# hivepod_interface_board_v1_1.net
KiCad netlist of a schematic drawn in EAGLE
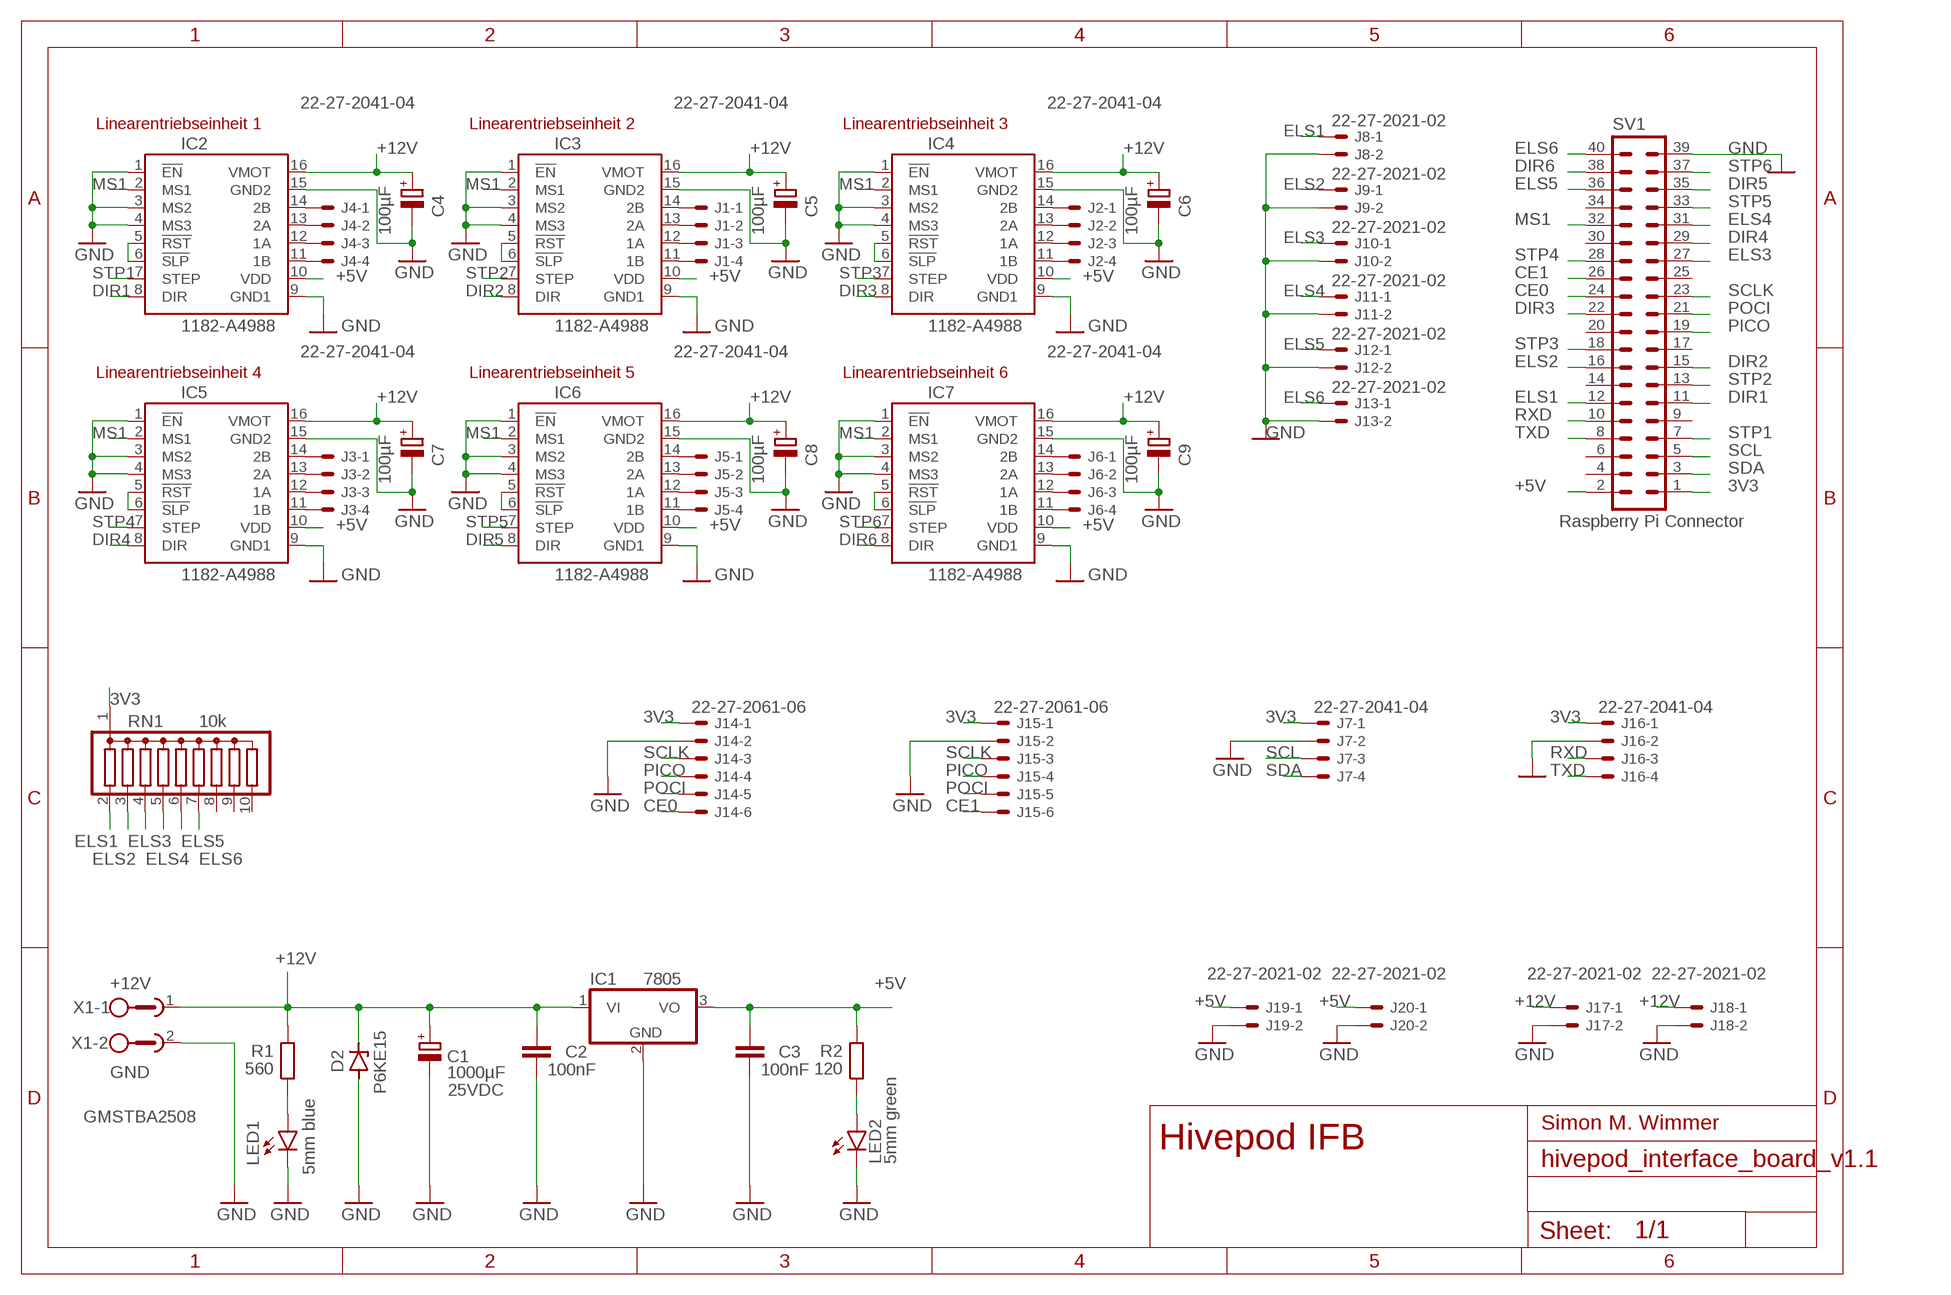
[diagram p0: schematic, sheet 1]

(export (version "E")
  (design (tool "Eeschema 10.0.6"))
  (components
    (comp (ref "C1")
      (value "1000µF")
      (footprint "eagle-import:E5-10,5")
      (libsource (lib "eagle-import") (part "rcl_334_CPOL-EUE5-10.5"))
    )
    (comp (ref "C2")
      (value "100nF")
      (footprint "eagle-import:C1206")
      (libsource (lib "eagle-import") (part "C-EUC1206"))
    )
    (comp (ref "C3")
      (value "100nF")
      (footprint "eagle-import:C1206")
      (libsource (lib "eagle-import") (part "C-EUC1206"))
    )
    (comp (ref "C4")
      (value "100µF")
      (footprint "eagle-import:E5-6")
      (libsource (lib "eagle-import") (part "CPOL-EUE5-6"))
    )
    (comp (ref "C5")
      (value "100µF")
      (footprint "eagle-import:E5-6")
      (libsource (lib "eagle-import") (part "CPOL-EUE5-6"))
    )
    (comp (ref "C6")
      (value "100µF")
      (footprint "eagle-import:E5-6")
      (libsource (lib "eagle-import") (part "CPOL-EUE5-6"))
    )
    (comp (ref "C7")
      (value "100µF")
      (footprint "eagle-import:E5-6")
      (libsource (lib "eagle-import") (part "CPOL-EUE5-6"))
    )
    (comp (ref "C8")
      (value "100µF")
      (footprint "eagle-import:E5-6")
      (libsource (lib "eagle-import") (part "CPOL-EUE5-6"))
    )
    (comp (ref "C9")
      (value "100µF")
      (footprint "eagle-import:E5-6")
      (libsource (lib "eagle-import") (part "CPOL-EUE5-6"))
    )
    (comp (ref "D2")
      (value "P6KE15")
      (footprint "eagle-import:F126Z12")
      (libsource (lib "eagle-import") (part "BZY97"))
    )
    (comp (ref "IC1")
      (value "7805")
      (footprint "eagle-import:TO220V")
      (libsource (lib "eagle-import") (part "78V"))
    )
    (comp (ref "IC2")
      (value "1182-A4988")
      (footprint "eagle-import:A4988")
      (libsource (lib "eagle-import") (part "1182-A4988"))
    )
    (comp (ref "IC3")
      (value "1182-A4988")
      (footprint "eagle-import:A4988")
      (libsource (lib "eagle-import") (part "1182-A4988"))
    )
    (comp (ref "IC4")
      (value "1182-A4988")
      (footprint "eagle-import:A4988")
      (libsource (lib "eagle-import") (part "1182-A4988"))
    )
    (comp (ref "IC5")
      (value "1182-A4988")
      (footprint "eagle-import:A4988")
      (libsource (lib "eagle-import") (part "1182-A4988"))
    )
    (comp (ref "IC6")
      (value "1182-A4988")
      (footprint "eagle-import:A4988")
      (libsource (lib "eagle-import") (part "1182-A4988"))
    )
    (comp (ref "IC7")
      (value "1182-A4988")
      (footprint "eagle-import:A4988")
      (libsource (lib "eagle-import") (part "1182-A4988"))
    )
    (comp (ref "J1")
      (value "22-27-2041-04")
      (footprint "eagle-import:6410-04")
      (fields (field (name "MF") "MOLEX"))
      (libsource (lib "eagle-import") (part "22-?-0427-2041"))
    )
    (comp (ref "J2")
      (value "22-27-2041-04")
      (footprint "eagle-import:6410-04")
      (fields (field (name "MF") "MOLEX"))
      (libsource (lib "eagle-import") (part "22-?-0427-2041"))
    )
    (comp (ref "J3")
      (value "22-27-2041-04")
      (footprint "eagle-import:6410-04")
      (fields (field (name "MF") "MOLEX"))
      (libsource (lib "eagle-import") (part "22-?-0427-2041"))
    )
    (comp (ref "J4")
      (value "22-27-2041-04")
      (footprint "eagle-import:6410-04")
      (fields (field (name "MF") "MOLEX"))
      (libsource (lib "eagle-import") (part "22-?-0427-2041"))
    )
    (comp (ref "J5")
      (value "22-27-2041-04")
      (footprint "eagle-import:6410-04")
      (fields (field (name "MF") "MOLEX"))
      (libsource (lib "eagle-import") (part "22-?-0427-2041"))
    )
    (comp (ref "J6")
      (value "22-27-2041-04")
      (footprint "eagle-import:6410-04")
      (fields (field (name "MF") "MOLEX"))
      (libsource (lib "eagle-import") (part "22-?-0427-2041"))
    )
    (comp (ref "J7")
      (value "22-27-2041-04")
      (footprint "eagle-import:6410-04")
      (fields (field (name "MF") "MOLEX"))
      (libsource (lib "eagle-import") (part "22-?-0427-2041"))
    )
    (comp (ref "J8")
      (value "22-27-2021-02")
      (footprint "eagle-import:6410-02")
      (fields (field (name "MF") "MOLEX"))
      (libsource (lib "eagle-import") (part "22-?-0227-2021"))
    )
    (comp (ref "J9")
      (value "22-27-2021-02")
      (footprint "eagle-import:6410-02")
      (fields (field (name "MF") "MOLEX"))
      (libsource (lib "eagle-import") (part "22-?-0227-2021"))
    )
    (comp (ref "J10")
      (value "22-27-2021-02")
      (footprint "eagle-import:6410-02")
      (fields (field (name "MF") "MOLEX"))
      (libsource (lib "eagle-import") (part "22-?-0227-2021"))
    )
    (comp (ref "J11")
      (value "22-27-2021-02")
      (footprint "eagle-import:6410-02")
      (fields (field (name "MF") "MOLEX"))
      (libsource (lib "eagle-import") (part "22-?-0227-2021"))
    )
    (comp (ref "J12")
      (value "22-27-2021-02")
      (footprint "eagle-import:6410-02")
      (fields (field (name "MF") "MOLEX"))
      (libsource (lib "eagle-import") (part "22-?-0227-2021"))
    )
    (comp (ref "J13")
      (value "22-27-2021-02")
      (footprint "eagle-import:6410-02")
      (fields (field (name "MF") "MOLEX"))
      (libsource (lib "eagle-import") (part "22-?-0227-2021"))
    )
    (comp (ref "J14")
      (value "22-27-2061-06")
      (footprint "eagle-import:6410-06")
      (libsource (lib "eagle-import") (part "22-?-0627-2061"))
    )
    (comp (ref "J15")
      (value "22-27-2061-06")
      (footprint "eagle-import:6410-06")
      (libsource (lib "eagle-import") (part "22-?-0627-2061"))
    )
    (comp (ref "J16")
      (value "22-27-2041-04")
      (footprint "eagle-import:6410-04")
      (fields (field (name "MF") "MOLEX"))
      (libsource (lib "eagle-import") (part "22-?-0427-2041"))
    )
    (comp (ref "J17")
      (value "22-27-2021-02")
      (footprint "eagle-import:6410-02")
      (fields (field (name "MF") "MOLEX"))
      (libsource (lib "eagle-import") (part "22-?-0227-2021"))
    )
    (comp (ref "J18")
      (value "22-27-2021-02")
      (footprint "eagle-import:6410-02")
      (fields (field (name "MF") "MOLEX"))
      (libsource (lib "eagle-import") (part "22-?-0227-2021"))
    )
    (comp (ref "J19")
      (value "22-27-2021-02")
      (footprint "eagle-import:6410-02")
      (fields (field (name "MF") "MOLEX"))
      (libsource (lib "eagle-import") (part "22-?-0227-2021"))
    )
    (comp (ref "J20")
      (value "22-27-2021-02")
      (footprint "eagle-import:6410-02")
      (fields (field (name "MF") "MOLEX"))
      (libsource (lib "eagle-import") (part "22-?-0227-2021"))
    )
    (comp (ref "LED1")
      (value "5mm blue")
      (footprint "eagle-import:LED5MM")
      (libsource (lib "eagle-import") (part "LED5MM"))
    )
    (comp (ref "LED2")
      (value "5mm green")
      (footprint "eagle-import:LED5MM")
      (libsource (lib "eagle-import") (part "LED5MM"))
    )
    (comp (ref "R1")
      (value "560")
      (footprint "eagle-import:R1206")
      (libsource (lib "eagle-import") (part "R-EU_R1206"))
    )
    (comp (ref "R2")
      (value "120")
      (footprint "eagle-import:R1206")
      (libsource (lib "eagle-import") (part "R-EU_R1206"))
    )
    (comp (ref "RN1")
      (value "10k")
      (footprint "eagle-import:SIL10")
      (libsource (lib "eagle-import") (part "G09R"))
    )
    (comp (ref "SV1")
      (value "Raspberry Pi Connector")
      (footprint "eagle-import:ML40")
      (libsource (lib "eagle-import") (part "ML40"))
    )
    (comp (ref "X1")
      (value "GMSTBA2508")
      (footprint "eagle-import:HOR-2")
      (libsource (lib "eagle-import") (part "GMSTBA2508"))
    )
  )
  (nets
    (net (code "1") (name "/+5V") (class "Default")
      (node (ref "C3") (pin "1") (pinfunction "1_1") (pintype "passive"))
      (node (ref "IC1") (pin "3") (pinfunction "VO_3") (pintype "passive"))
      (node (ref "IC2") (pin "10") (pinfunction "VDD_10") (pintype "power_in"))
      (node (ref "IC3") (pin "10") (pinfunction "VDD_10") (pintype "power_in"))
      (node (ref "IC4") (pin "10") (pinfunction "VDD_10") (pintype "power_in"))
      (node (ref "IC5") (pin "10") (pinfunction "VDD_10") (pintype "power_in"))
      (node (ref "IC6") (pin "10") (pinfunction "VDD_10") (pintype "power_in"))
      (node (ref "IC7") (pin "10") (pinfunction "VDD_10") (pintype "power_in"))
      (node (ref "J19") (pin "1") (pinfunction "S_1") (pintype "passive"))
      (node (ref "J20") (pin "1") (pinfunction "S_1") (pintype "passive"))
      (node (ref "R2") (pin "2") (pinfunction "2_2") (pintype "passive"))
      (node (ref "SV1") (pin "2") (pinfunction "2_2") (pintype "passive"))
    )
    (net (code "2") (name "/+12V") (class "Default")
      (node (ref "C1") (pin "+") (pinfunction "+_+") (pintype "passive"))
      (node (ref "C2") (pin "1") (pinfunction "1_1") (pintype "passive"))
      (node (ref "C4") (pin "+") (pinfunction "+_+") (pintype "passive"))
      (node (ref "C5") (pin "+") (pinfunction "+_+") (pintype "passive"))
      (node (ref "C6") (pin "+") (pinfunction "+_+") (pintype "passive"))
      (node (ref "C7") (pin "+") (pinfunction "+_+") (pintype "passive"))
      (node (ref "C8") (pin "+") (pinfunction "+_+") (pintype "passive"))
      (node (ref "C9") (pin "+") (pinfunction "+_+") (pintype "passive"))
      (node (ref "D2") (pin "C") (pinfunction "C_C") (pintype "passive"))
      (node (ref "IC1") (pin "1") (pinfunction "VI_1") (pintype "input"))
      (node (ref "IC2") (pin "16") (pinfunction "VMOT_16") (pintype "power_in"))
      (node (ref "IC3") (pin "16") (pinfunction "VMOT_16") (pintype "power_in"))
      (node (ref "IC4") (pin "16") (pinfunction "VMOT_16") (pintype "power_in"))
      (node (ref "IC5") (pin "16") (pinfunction "VMOT_16") (pintype "power_in"))
      (node (ref "IC6") (pin "16") (pinfunction "VMOT_16") (pintype "power_in"))
      (node (ref "IC7") (pin "16") (pinfunction "VMOT_16") (pintype "power_in"))
      (node (ref "J17") (pin "1") (pinfunction "S_1") (pintype "passive"))
      (node (ref "J18") (pin "1") (pinfunction "S_1") (pintype "passive"))
      (node (ref "R1") (pin "2") (pinfunction "2_2") (pintype "passive"))
      (node (ref "X1") (pin "1") (pinfunction "1_1") (pintype "passive"))
    )
    (net (code "3") (name "/3V3") (class "Default")
      (node (ref "J14") (pin "1") (pinfunction "S_1") (pintype "passive"))
      (node (ref "J15") (pin "1") (pinfunction "S_1") (pintype "passive"))
      (node (ref "J16") (pin "1") (pinfunction "S_1") (pintype "passive"))
      (node (ref "J7") (pin "1") (pinfunction "S_1") (pintype "passive"))
      (node (ref "RN1") (pin "1") (pinfunction "1_1") (pintype "passive"))
      (node (ref "SV1") (pin "1") (pinfunction "1_1") (pintype "passive"))
    )
    (net (code "4") (name "/CE0") (class "Default")
      (node (ref "J14") (pin "6") (pinfunction "S_6") (pintype "passive"))
      (node (ref "SV1") (pin "24") (pinfunction "24_24") (pintype "passive"))
    )
    (net (code "5") (name "/CE1") (class "Default")
      (node (ref "J15") (pin "6") (pinfunction "S_6") (pintype "passive"))
      (node (ref "SV1") (pin "26") (pinfunction "26_26") (pintype "passive"))
    )
    (net (code "6") (name "/DIR1") (class "Default")
      (node (ref "IC2") (pin "8") (pinfunction "DIR_8") (pintype "input"))
      (node (ref "SV1") (pin "11") (pinfunction "11_11") (pintype "passive"))
    )
    (net (code "7") (name "/DIR2") (class "Default")
      (node (ref "IC3") (pin "8") (pinfunction "DIR_8") (pintype "input"))
      (node (ref "SV1") (pin "15") (pinfunction "15_15") (pintype "passive"))
    )
    (net (code "8") (name "/DIR3") (class "Default")
      (node (ref "IC4") (pin "8") (pinfunction "DIR_8") (pintype "input"))
      (node (ref "SV1") (pin "22") (pinfunction "22_22") (pintype "passive"))
    )
    (net (code "9") (name "/DIR4") (class "Default")
      (node (ref "IC5") (pin "8") (pinfunction "DIR_8") (pintype "input"))
      (node (ref "SV1") (pin "29") (pinfunction "29_29") (pintype "passive"))
    )
    (net (code "10") (name "/DIR5") (class "Default")
      (node (ref "IC6") (pin "8") (pinfunction "DIR_8") (pintype "input"))
      (node (ref "SV1") (pin "35") (pinfunction "35_35") (pintype "passive"))
    )
    (net (code "11") (name "/DIR6") (class "Default")
      (node (ref "IC7") (pin "8") (pinfunction "DIR_8") (pintype "input"))
      (node (ref "SV1") (pin "38") (pinfunction "38_38") (pintype "passive"))
    )
    (net (code "12") (name "/ELS1") (class "Default")
      (node (ref "J8") (pin "1") (pinfunction "S_1") (pintype "passive"))
      (node (ref "RN1") (pin "2") (pinfunction "2_2") (pintype "passive"))
      (node (ref "SV1") (pin "12") (pinfunction "12_12") (pintype "passive"))
    )
    (net (code "13") (name "/ELS2") (class "Default")
      (node (ref "J9") (pin "1") (pinfunction "S_1") (pintype "passive"))
      (node (ref "RN1") (pin "3") (pinfunction "3_3") (pintype "passive"))
      (node (ref "SV1") (pin "16") (pinfunction "16_16") (pintype "passive"))
    )
    (net (code "14") (name "/ELS3") (class "Default")
      (node (ref "J10") (pin "1") (pinfunction "S_1") (pintype "passive"))
      (node (ref "RN1") (pin "4") (pinfunction "4_4") (pintype "passive"))
      (node (ref "SV1") (pin "27") (pinfunction "27_27") (pintype "passive"))
    )
    (net (code "15") (name "/ELS4") (class "Default")
      (node (ref "J11") (pin "1") (pinfunction "S_1") (pintype "passive"))
      (node (ref "RN1") (pin "5") (pinfunction "5_5") (pintype "passive"))
      (node (ref "SV1") (pin "31") (pinfunction "31_31") (pintype "passive"))
    )
    (net (code "16") (name "/ELS5") (class "Default")
      (node (ref "J12") (pin "1") (pinfunction "S_1") (pintype "passive"))
      (node (ref "RN1") (pin "6") (pinfunction "6_6") (pintype "passive"))
      (node (ref "SV1") (pin "36") (pinfunction "36_36") (pintype "passive"))
    )
    (net (code "17") (name "/ELS6") (class "Default")
      (node (ref "J13") (pin "1") (pinfunction "S_1") (pintype "passive"))
      (node (ref "RN1") (pin "7") (pinfunction "7_7") (pintype "passive"))
      (node (ref "SV1") (pin "40") (pinfunction "40_40") (pintype "passive"))
    )
    (net (code "18") (name "/MS1") (class "Default")
      (node (ref "IC2") (pin "2") (pinfunction "MS1_2") (pintype "passive"))
      (node (ref "IC3") (pin "2") (pinfunction "MS1_2") (pintype "passive"))
      (node (ref "IC4") (pin "2") (pinfunction "MS1_2") (pintype "passive"))
      (node (ref "IC5") (pin "2") (pinfunction "MS1_2") (pintype "passive"))
      (node (ref "IC6") (pin "2") (pinfunction "MS1_2") (pintype "passive"))
      (node (ref "IC7") (pin "2") (pinfunction "MS1_2") (pintype "passive"))
      (node (ref "SV1") (pin "32") (pinfunction "32_32") (pintype "passive"))
    )
    (net (code "19") (name "/PICO") (class "Default")
      (node (ref "J14") (pin "4") (pinfunction "S_4") (pintype "passive"))
      (node (ref "J15") (pin "4") (pinfunction "S_4") (pintype "passive"))
      (node (ref "SV1") (pin "19") (pinfunction "19_19") (pintype "passive"))
    )
    (net (code "20") (name "/POCI") (class "Default")
      (node (ref "J14") (pin "5") (pinfunction "S_5") (pintype "passive"))
      (node (ref "J15") (pin "5") (pinfunction "S_5") (pintype "passive"))
      (node (ref "SV1") (pin "21") (pinfunction "21_21") (pintype "passive"))
    )
    (net (code "21") (name "/RXD") (class "Default")
      (node (ref "J16") (pin "3") (pinfunction "S_3") (pintype "passive"))
      (node (ref "SV1") (pin "10") (pinfunction "10_10") (pintype "passive"))
    )
    (net (code "22") (name "/SCL") (class "Default")
      (node (ref "J7") (pin "3") (pinfunction "S_3") (pintype "passive"))
      (node (ref "SV1") (pin "5") (pinfunction "5_5") (pintype "passive"))
    )
    (net (code "23") (name "/SCLK") (class "Default")
      (node (ref "J14") (pin "3") (pinfunction "S_3") (pintype "passive"))
      (node (ref "J15") (pin "3") (pinfunction "S_3") (pintype "passive"))
      (node (ref "SV1") (pin "23") (pinfunction "23_23") (pintype "passive"))
    )
    (net (code "24") (name "/SDA") (class "Default")
      (node (ref "J7") (pin "4") (pinfunction "S_4") (pintype "passive"))
      (node (ref "SV1") (pin "3") (pinfunction "3_3") (pintype "passive"))
    )
    (net (code "25") (name "/STP1") (class "Default")
      (node (ref "IC2") (pin "7") (pinfunction "STEP_7") (pintype "input"))
      (node (ref "SV1") (pin "7") (pinfunction "7_7") (pintype "passive"))
    )
    (net (code "26") (name "/STP2") (class "Default")
      (node (ref "IC3") (pin "7") (pinfunction "STEP_7") (pintype "input"))
      (node (ref "SV1") (pin "13") (pinfunction "13_13") (pintype "passive"))
    )
    (net (code "27") (name "/STP3") (class "Default")
      (node (ref "IC4") (pin "7") (pinfunction "STEP_7") (pintype "input"))
      (node (ref "SV1") (pin "18") (pinfunction "18_18") (pintype "passive"))
    )
    (net (code "28") (name "/STP4") (class "Default")
      (node (ref "IC5") (pin "7") (pinfunction "STEP_7") (pintype "input"))
      (node (ref "SV1") (pin "28") (pinfunction "28_28") (pintype "passive"))
    )
    (net (code "29") (name "/STP5") (class "Default")
      (node (ref "IC6") (pin "7") (pinfunction "STEP_7") (pintype "input"))
      (node (ref "SV1") (pin "33") (pinfunction "33_33") (pintype "passive"))
    )
    (net (code "30") (name "/STP6") (class "Default")
      (node (ref "IC7") (pin "7") (pinfunction "STEP_7") (pintype "input"))
      (node (ref "SV1") (pin "37") (pinfunction "37_37") (pintype "passive"))
    )
    (net (code "31") (name "/TXD") (class "Default")
      (node (ref "J16") (pin "4") (pinfunction "S_4") (pintype "passive"))
      (node (ref "SV1") (pin "8") (pinfunction "8_8") (pintype "passive"))
    )
    (net (code "32") (name "GND") (class "Default")
      (node (ref "C1") (pin "-") (pinfunction "-_-") (pintype "passive"))
      (node (ref "C2") (pin "2") (pinfunction "2_2") (pintype "passive"))
      (node (ref "C3") (pin "2") (pinfunction "2_2") (pintype "passive"))
      (node (ref "C4") (pin "-") (pinfunction "-_-") (pintype "passive"))
      (node (ref "C5") (pin "-") (pinfunction "-_-") (pintype "passive"))
      (node (ref "C6") (pin "-") (pinfunction "-_-") (pintype "passive"))
      (node (ref "C7") (pin "-") (pinfunction "-_-") (pintype "passive"))
      (node (ref "C8") (pin "-") (pinfunction "-_-") (pintype "passive"))
      (node (ref "C9") (pin "-") (pinfunction "-_-") (pintype "passive"))
      (node (ref "D2") (pin "A") (pinfunction "A_A") (pintype "passive"))
      (node (ref "IC1") (pin "2") (pinfunction "GND_2") (pintype "passive"))
      (node (ref "IC2") (pin "1") (pinfunction "~{EN}_1") (pintype "passive"))
      (node (ref "IC2") (pin "15") (pinfunction "GND2_15") (pintype "power_in"))
      (node (ref "IC2") (pin "3") (pinfunction "MS2_3") (pintype "passive"))
      (node (ref "IC2") (pin "4") (pinfunction "MS3_4") (pintype "passive"))
      (node (ref "IC2") (pin "9") (pinfunction "GND1_9") (pintype "power_in"))
      (node (ref "IC3") (pin "1") (pinfunction "~{EN}_1") (pintype "passive"))
      (node (ref "IC3") (pin "15") (pinfunction "GND2_15") (pintype "power_in"))
      (node (ref "IC3") (pin "3") (pinfunction "MS2_3") (pintype "passive"))
      (node (ref "IC3") (pin "4") (pinfunction "MS3_4") (pintype "passive"))
      (node (ref "IC3") (pin "9") (pinfunction "GND1_9") (pintype "power_in"))
      (node (ref "IC4") (pin "1") (pinfunction "~{EN}_1") (pintype "passive"))
      (node (ref "IC4") (pin "15") (pinfunction "GND2_15") (pintype "power_in"))
      (node (ref "IC4") (pin "3") (pinfunction "MS2_3") (pintype "passive"))
      (node (ref "IC4") (pin "4") (pinfunction "MS3_4") (pintype "passive"))
      (node (ref "IC4") (pin "9") (pinfunction "GND1_9") (pintype "power_in"))
      (node (ref "IC5") (pin "1") (pinfunction "~{EN}_1") (pintype "passive"))
      (node (ref "IC5") (pin "15") (pinfunction "GND2_15") (pintype "power_in"))
      (node (ref "IC5") (pin "3") (pinfunction "MS2_3") (pintype "passive"))
      (node (ref "IC5") (pin "4") (pinfunction "MS3_4") (pintype "passive"))
      (node (ref "IC5") (pin "9") (pinfunction "GND1_9") (pintype "power_in"))
      (node (ref "IC6") (pin "1") (pinfunction "~{EN}_1") (pintype "passive"))
      (node (ref "IC6") (pin "15") (pinfunction "GND2_15") (pintype "power_in"))
      (node (ref "IC6") (pin "3") (pinfunction "MS2_3") (pintype "passive"))
      (node (ref "IC6") (pin "4") (pinfunction "MS3_4") (pintype "passive"))
      (node (ref "IC6") (pin "9") (pinfunction "GND1_9") (pintype "power_in"))
      (node (ref "IC7") (pin "1") (pinfunction "~{EN}_1") (pintype "passive"))
      (node (ref "IC7") (pin "15") (pinfunction "GND2_15") (pintype "power_in"))
      (node (ref "IC7") (pin "3") (pinfunction "MS2_3") (pintype "passive"))
      (node (ref "IC7") (pin "4") (pinfunction "MS3_4") (pintype "passive"))
      (node (ref "IC7") (pin "9") (pinfunction "GND1_9") (pintype "power_in"))
      (node (ref "J10") (pin "2") (pinfunction "S_2") (pintype "passive"))
      (node (ref "J11") (pin "2") (pinfunction "S_2") (pintype "passive"))
      (node (ref "J12") (pin "2") (pinfunction "S_2") (pintype "passive"))
      (node (ref "J13") (pin "2") (pinfunction "S_2") (pintype "passive"))
      (node (ref "J14") (pin "2") (pinfunction "S_2") (pintype "passive"))
      (node (ref "J15") (pin "2") (pinfunction "S_2") (pintype "passive"))
      (node (ref "J16") (pin "2") (pinfunction "S_2") (pintype "passive"))
      (node (ref "J17") (pin "2") (pinfunction "S_2") (pintype "passive"))
      (node (ref "J18") (pin "2") (pinfunction "S_2") (pintype "passive"))
      (node (ref "J19") (pin "2") (pinfunction "S_2") (pintype "passive"))
      (node (ref "J20") (pin "2") (pinfunction "S_2") (pintype "passive"))
      (node (ref "J7") (pin "2") (pinfunction "S_2") (pintype "passive"))
      (node (ref "J8") (pin "2") (pinfunction "S_2") (pintype "passive"))
      (node (ref "J9") (pin "2") (pinfunction "S_2") (pintype "passive"))
      (node (ref "LED1") (pin "K") (pinfunction "C_K") (pintype "passive"))
      (node (ref "LED2") (pin "K") (pinfunction "C_K") (pintype "passive"))
      (node (ref "SV1") (pin "39") (pinfunction "39_39") (pintype "passive"))
      (node (ref "X1") (pin "2") (pinfunction "1_2") (pintype "passive"))
    )
    (net (code "33") (name "Net-(IC2-1A)") (class "Default")
      (node (ref "IC2") (pin "12") (pinfunction "1A_12") (pintype "output"))
      (node (ref "J4") (pin "3") (pinfunction "S_3") (pintype "passive"))
    )
    (net (code "34") (name "Net-(IC2-1B)") (class "Default")
      (node (ref "IC2") (pin "11") (pinfunction "1B_11") (pintype "output"))
      (node (ref "J4") (pin "4") (pinfunction "S_4") (pintype "passive"))
    )
    (net (code "35") (name "Net-(IC2-2A)") (class "Default")
      (node (ref "IC2") (pin "13") (pinfunction "2A_13") (pintype "output"))
      (node (ref "J4") (pin "2") (pinfunction "S_2") (pintype "passive"))
    )
    (net (code "36") (name "Net-(IC2-2B)") (class "Default")
      (node (ref "IC2") (pin "14") (pinfunction "2B_14") (pintype "output"))
      (node (ref "J4") (pin "1") (pinfunction "S_1") (pintype "passive"))
    )
    (net (code "37") (name "Net-(IC2-~{RST})") (class "Default")
      (node (ref "IC2") (pin "5") (pinfunction "~{RST}_5") (pintype "passive"))
      (node (ref "IC2") (pin "6") (pinfunction "~{SLP}_6") (pintype "passive"))
    )
    (net (code "38") (name "Net-(IC3-1A)") (class "Default")
      (node (ref "IC3") (pin "12") (pinfunction "1A_12") (pintype "output"))
      (node (ref "J1") (pin "3") (pinfunction "S_3") (pintype "passive"))
    )
    (net (code "39") (name "Net-(IC3-1B)") (class "Default")
      (node (ref "IC3") (pin "11") (pinfunction "1B_11") (pintype "output"))
      (node (ref "J1") (pin "4") (pinfunction "S_4") (pintype "passive"))
    )
    (net (code "40") (name "Net-(IC3-2A)") (class "Default")
      (node (ref "IC3") (pin "13") (pinfunction "2A_13") (pintype "output"))
      (node (ref "J1") (pin "2") (pinfunction "S_2") (pintype "passive"))
    )
    (net (code "41") (name "Net-(IC3-2B)") (class "Default")
      (node (ref "IC3") (pin "14") (pinfunction "2B_14") (pintype "output"))
      (node (ref "J1") (pin "1") (pinfunction "S_1") (pintype "passive"))
    )
    (net (code "42") (name "Net-(IC3-~{RST})") (class "Default")
      (node (ref "IC3") (pin "5") (pinfunction "~{RST}_5") (pintype "passive"))
      (node (ref "IC3") (pin "6") (pinfunction "~{SLP}_6") (pintype "passive"))
    )
    (net (code "43") (name "Net-(IC4-1A)") (class "Default")
      (node (ref "IC4") (pin "12") (pinfunction "1A_12") (pintype "output"))
      (node (ref "J2") (pin "3") (pinfunction "S_3") (pintype "passive"))
    )
    (net (code "44") (name "Net-(IC4-1B)") (class "Default")
      (node (ref "IC4") (pin "11") (pinfunction "1B_11") (pintype "output"))
      (node (ref "J2") (pin "4") (pinfunction "S_4") (pintype "passive"))
    )
    (net (code "45") (name "Net-(IC4-2A)") (class "Default")
      (node (ref "IC4") (pin "13") (pinfunction "2A_13") (pintype "output"))
      (node (ref "J2") (pin "2") (pinfunction "S_2") (pintype "passive"))
    )
    (net (code "46") (name "Net-(IC4-2B)") (class "Default")
      (node (ref "IC4") (pin "14") (pinfunction "2B_14") (pintype "output"))
      (node (ref "J2") (pin "1") (pinfunction "S_1") (pintype "passive"))
    )
    (net (code "47") (name "Net-(IC4-~{RST})") (class "Default")
      (node (ref "IC4") (pin "5") (pinfunction "~{RST}_5") (pintype "passive"))
      (node (ref "IC4") (pin "6") (pinfunction "~{SLP}_6") (pintype "passive"))
    )
    (net (code "48") (name "Net-(IC5-1A)") (class "Default")
      (node (ref "IC5") (pin "12") (pinfunction "1A_12") (pintype "output"))
      (node (ref "J3") (pin "3") (pinfunction "S_3") (pintype "passive"))
    )
    (net (code "49") (name "Net-(IC5-1B)") (class "Default")
      (node (ref "IC5") (pin "11") (pinfunction "1B_11") (pintype "output"))
      (node (ref "J3") (pin "4") (pinfunction "S_4") (pintype "passive"))
    )
    (net (code "50") (name "Net-(IC5-2A)") (class "Default")
      (node (ref "IC5") (pin "13") (pinfunction "2A_13") (pintype "output"))
      (node (ref "J3") (pin "2") (pinfunction "S_2") (pintype "passive"))
    )
    (net (code "51") (name "Net-(IC5-2B)") (class "Default")
      (node (ref "IC5") (pin "14") (pinfunction "2B_14") (pintype "output"))
      (node (ref "J3") (pin "1") (pinfunction "S_1") (pintype "passive"))
    )
    (net (code "52") (name "Net-(IC5-~{RST})") (class "Default")
      (node (ref "IC5") (pin "5") (pinfunction "~{RST}_5") (pintype "passive"))
      (node (ref "IC5") (pin "6") (pinfunction "~{SLP}_6") (pintype "passive"))
    )
    (net (code "53") (name "Net-(IC6-1A)") (class "Default")
      (node (ref "IC6") (pin "12") (pinfunction "1A_12") (pintype "output"))
      (node (ref "J5") (pin "3") (pinfunction "S_3") (pintype "passive"))
    )
    (net (code "54") (name "Net-(IC6-1B)") (class "Default")
      (node (ref "IC6") (pin "11") (pinfunction "1B_11") (pintype "output"))
      (node (ref "J5") (pin "4") (pinfunction "S_4") (pintype "passive"))
    )
    (net (code "55") (name "Net-(IC6-2A)") (class "Default")
      (node (ref "IC6") (pin "13") (pinfunction "2A_13") (pintype "output"))
      (node (ref "J5") (pin "2") (pinfunction "S_2") (pintype "passive"))
    )
    (net (code "56") (name "Net-(IC6-2B)") (class "Default")
      (node (ref "IC6") (pin "14") (pinfunction "2B_14") (pintype "output"))
      (node (ref "J5") (pin "1") (pinfunction "S_1") (pintype "passive"))
    )
    (net (code "57") (name "Net-(IC6-~{RST})") (class "Default")
      (node (ref "IC6") (pin "5") (pinfunction "~{RST}_5") (pintype "passive"))
      (node (ref "IC6") (pin "6") (pinfunction "~{SLP}_6") (pintype "passive"))
    )
    (net (code "58") (name "Net-(IC7-1A)") (class "Default")
      (node (ref "IC7") (pin "12") (pinfunction "1A_12") (pintype "output"))
      (node (ref "J6") (pin "3") (pinfunction "S_3") (pintype "passive"))
    )
    (net (code "59") (name "Net-(IC7-1B)") (class "Default")
      (node (ref "IC7") (pin "11") (pinfunction "1B_11") (pintype "output"))
      (node (ref "J6") (pin "4") (pinfunction "S_4") (pintype "passive"))
    )
    (net (code "60") (name "Net-(IC7-2A)") (class "Default")
      (node (ref "IC7") (pin "13") (pinfunction "2A_13") (pintype "output"))
      (node (ref "J6") (pin "2") (pinfunction "S_2") (pintype "passive"))
    )
    (net (code "61") (name "Net-(IC7-2B)") (class "Default")
      (node (ref "IC7") (pin "14") (pinfunction "2B_14") (pintype "output"))
      (node (ref "J6") (pin "1") (pinfunction "S_1") (pintype "passive"))
    )
    (net (code "62") (name "Net-(IC7-~{RST})") (class "Default")
      (node (ref "IC7") (pin "5") (pinfunction "~{RST}_5") (pintype "passive"))
      (node (ref "IC7") (pin "6") (pinfunction "~{SLP}_6") (pintype "passive"))
    )
    (net (code "63") (name "Net-(LED1-PadA)") (class "Default")
      (node (ref "LED1") (pin "A") (pinfunction "A_A") (pintype "passive"))
      (node (ref "R1") (pin "1") (pinfunction "1_1") (pintype "passive"))
    )
    (net (code "64") (name "Net-(LED2-PadA)") (class "Default")
      (node (ref "LED2") (pin "A") (pinfunction "A_A") (pintype "passive"))
      (node (ref "R2") (pin "1") (pinfunction "1_1") (pintype "passive"))
    )
    (net (code "65") (name "unconnected-(RN1-Pad8)") (class "Default")
      (node (ref "RN1") (pin "8") (pinfunction "8_8") (pintype "passive"))
    )
    (net (code "66") (name "unconnected-(RN1-Pad9)") (class "Default")
      (node (ref "RN1") (pin "9") (pinfunction "9_9") (pintype "passive"))
    )
    (net (code "67") (name "unconnected-(RN1-Pad10)") (class "Default")
      (node (ref "RN1") (pin "10") (pinfunction "10_10") (pintype "passive"))
    )
    (net (code "68") (name "unconnected-(SV1-Pad4)") (class "Default")
      (node (ref "SV1") (pin "4") (pinfunction "4_4") (pintype "passive"))
    )
    (net (code "69") (name "unconnected-(SV1-Pad6)") (class "Default")
      (node (ref "SV1") (pin "6") (pinfunction "6_6") (pintype "passive"))
    )
    (net (code "70") (name "unconnected-(SV1-Pad9)") (class "Default")
      (node (ref "SV1") (pin "9") (pinfunction "9_9") (pintype "passive"))
    )
    (net (code "71") (name "unconnected-(SV1-Pad14)") (class "Default")
      (node (ref "SV1") (pin "14") (pinfunction "14_14") (pintype "passive"))
    )
    (net (code "72") (name "unconnected-(SV1-Pad17)") (class "Default")
      (node (ref "SV1") (pin "17") (pinfunction "17_17") (pintype "passive"))
    )
    (net (code "73") (name "unconnected-(SV1-Pad20)") (class "Default")
      (node (ref "SV1") (pin "20") (pinfunction "20_20") (pintype "passive"))
    )
    (net (code "74") (name "unconnected-(SV1-Pad25)") (class "Default")
      (node (ref "SV1") (pin "25") (pinfunction "25_25") (pintype "passive"))
    )
    (net (code "75") (name "unconnected-(SV1-Pad30)") (class "Default")
      (node (ref "SV1") (pin "30") (pinfunction "30_30") (pintype "passive"))
    )
    (net (code "76") (name "unconnected-(SV1-Pad34)") (class "Default")
      (node (ref "SV1") (pin "34") (pinfunction "34_34") (pintype "passive"))
    )
  )
)
